# ArduinoProMini_NRF24_DHT.net
KiCad netlist of a schematic drawn in EAGLE
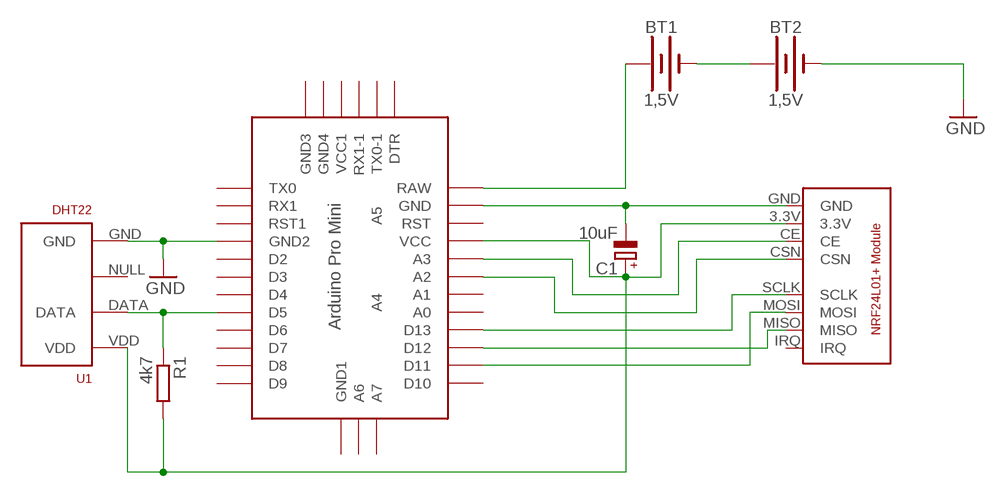
[diagram p0: schematic, sheet 1]

(export (version "E")
  (design (tool "Eeschema 10.0.6"))
  (components
    (comp (ref "BT1")
      (value "1,5V")
      (footprint "eagle-import:BATTERY-AA")
      (libsource (lib "eagle-import") (part "BATTERY-AA"))
    )
    (comp (ref "BT2")
      (value "1,5V")
      (footprint "eagle-import:BATTERY-AA")
      (libsource (lib "eagle-import") (part "BATTERY-AA"))
    )
    (comp (ref "C1")
      (value "10uF")
      (footprint "eagle-import:E2-5")
      (libsource (lib "eagle-import") (part "CPOL-EUE2-5"))
    )
    (comp (ref "R1")
      (value "4k7")
      (footprint "eagle-import:0204_7")
      (libsource (lib "eagle-import") (part "R-EU_0204/7"))
    )
    (comp (ref "U$1")
      (value "ABK-PRO-MINI")
      (footprint "eagle-import:ABK-PRO-MINI")
      (libsource (lib "eagle-import") (part "ABK-PRO-MINI"))
    )
    (comp (ref "U$2")
      (value "NRF24L01+MODULE")
      (footprint "eagle-import:NRF24L01+MODULE")
      (libsource (lib "eagle-import") (part "NRF24L01+MODULE"))
    )
    (comp (ref "U1")
      (value "DHT22")
      (footprint "eagle-import:RHT03_DHT-22_RA")
      (libsource (lib "eagle-import") (part "RHT03_DHT-22_AM2302RA"))
    )
  )
  (nets
    (net (code "1") (name "GND") (class "Default")
      (node (ref "BT2") (pin "GND@1") (pinfunction "-_GND@1") (pintype "power_in"))
      (node (ref "C1") (pin "-") (pinfunction "-_-") (pintype "passive"))
      (node (ref "U$1") (pin "GND") (pinfunction "GND_GND") (pintype "bidirectional"))
      (node (ref "U$1") (pin "GND1") (pinfunction "GND2_GND1") (pintype "bidirectional"))
      (node (ref "U$2") (pin "GND") (pinfunction "GND_GND") (pintype "power_in"))
      (node (ref "U1") (pin "GND") (pinfunction "GND_GND") (pintype "power_in"))
    )
    (net (code "2") (name "Net-(BT1-+)") (class "Default")
      (node (ref "BT1") (pin "PWR@1") (pinfunction "+_PWR@1") (pintype "power_in"))
      (node (ref "U$1") (pin "RAW") (pinfunction "RAW_RAW") (pintype "bidirectional"))
    )
    (net (code "3") (name "Net-(BT1--)") (class "Default")
      (node (ref "BT1") (pin "GND@1") (pinfunction "-_GND@1") (pintype "power_in"))
      (node (ref "BT2") (pin "PWR@1") (pinfunction "+_PWR@1") (pintype "power_in"))
    )
    (net (code "4") (name "Net-(C1-Pad+)") (class "Default")
      (node (ref "C1") (pin "+") (pinfunction "+_+") (pintype "passive"))
      (node (ref "R1") (pin "2") (pinfunction "2_2") (pintype "passive"))
      (node (ref "U$1") (pin "VCC") (pinfunction "VCC_VCC") (pintype "bidirectional"))
      (node (ref "U$2") (pin "3.3V") (pinfunction "3.3V_3.3V") (pintype "power_in"))
      (node (ref "U1") (pin "VDD") (pinfunction "VDD_VDD") (pintype "power_in"))
    )
    (net (code "5") (name "Net-(R1-Pad1)") (class "Default")
      (node (ref "R1") (pin "1") (pinfunction "1_1") (pintype "passive"))
      (node (ref "U$1") (pin "D5") (pinfunction "D5_D5") (pintype "bidirectional"))
      (node (ref "U1") (pin "DATA") (pinfunction "DATA_DATA") (pintype "bidirectional"))
    )
    (net (code "6") (name "Net-(U$1-PadA2)") (class "Default")
      (node (ref "U$1") (pin "A2") (pinfunction "A2_A2") (pintype "bidirectional"))
      (node (ref "U$2") (pin "CSN") (pinfunction "CSN_CSN") (pintype "bidirectional"))
    )
    (net (code "7") (name "Net-(U$1-PadA3)") (class "Default")
      (node (ref "U$1") (pin "A3") (pinfunction "A3_A3") (pintype "bidirectional"))
      (node (ref "U$2") (pin "CE") (pinfunction "CE_CE") (pintype "bidirectional"))
    )
    (net (code "8") (name "Net-(U$1-PadD11)") (class "Default")
      (node (ref "U$1") (pin "D11") (pinfunction "D11_D11") (pintype "bidirectional"))
      (node (ref "U$2") (pin "MOSI") (pinfunction "MOSI_MOSI") (pintype "bidirectional"))
    )
    (net (code "9") (name "Net-(U$1-PadD12)") (class "Default")
      (node (ref "U$1") (pin "D12") (pinfunction "D12_D12") (pintype "bidirectional"))
      (node (ref "U$2") (pin "MISO") (pinfunction "MISO_MISO") (pintype "bidirectional"))
    )
    (net (code "10") (name "Net-(U$1-PadD13)") (class "Default")
      (node (ref "U$1") (pin "D13") (pinfunction "D13_D13") (pintype "bidirectional"))
      (node (ref "U$2") (pin "SCLK") (pinfunction "SCLK_SCLK") (pintype "bidirectional"))
    )
    (net (code "11") (name "unconnected-(U$1-GND1-PadGND4)") (class "Default")
      (node (ref "U$1") (pin "GND4") (pinfunction "GND1_GND4") (pintype "bidirectional"))
    )
    (net (code "12") (name "unconnected-(U$1-GND3-PadGND2)") (class "Default")
      (node (ref "U$1") (pin "GND2") (pinfunction "GND3_GND2") (pintype "bidirectional"))
    )
    (net (code "13") (name "unconnected-(U$1-GND4-PadGND3)") (class "Default")
      (node (ref "U$1") (pin "GND3") (pinfunction "GND4_GND3") (pintype "bidirectional"))
    )
    (net (code "14") (name "unconnected-(U$1-PadA0)") (class "Default")
      (node (ref "U$1") (pin "A0") (pinfunction "A0_A0") (pintype "bidirectional"))
    )
    (net (code "15") (name "unconnected-(U$1-PadA1)") (class "Default")
      (node (ref "U$1") (pin "A1") (pinfunction "A1_A1") (pintype "bidirectional"))
    )
    (net (code "16") (name "unconnected-(U$1-PadA4)") (class "Default")
      (node (ref "U$1") (pin "A4") (pinfunction "A4_A4") (pintype "bidirectional"))
    )
    (net (code "17") (name "unconnected-(U$1-PadA5)") (class "Default")
      (node (ref "U$1") (pin "A5") (pinfunction "A5_A5") (pintype "bidirectional"))
    )
    (net (code "18") (name "unconnected-(U$1-PadA6)") (class "Default")
      (node (ref "U$1") (pin "A6") (pinfunction "A6_A6") (pintype "bidirectional"))
    )
    (net (code "19") (name "unconnected-(U$1-PadA7)") (class "Default")
      (node (ref "U$1") (pin "A7") (pinfunction "A7_A7") (pintype "bidirectional"))
    )
    (net (code "20") (name "unconnected-(U$1-PadD2)") (class "Default")
      (node (ref "U$1") (pin "D2") (pinfunction "D2_D2") (pintype "bidirectional"))
    )
    (net (code "21") (name "unconnected-(U$1-PadD3)") (class "Default")
      (node (ref "U$1") (pin "D3") (pinfunction "D3_D3") (pintype "bidirectional"))
    )
    (net (code "22") (name "unconnected-(U$1-PadD4)") (class "Default")
      (node (ref "U$1") (pin "D4") (pinfunction "D4_D4") (pintype "bidirectional"))
    )
    (net (code "23") (name "unconnected-(U$1-PadD6)") (class "Default")
      (node (ref "U$1") (pin "D6") (pinfunction "D6_D6") (pintype "bidirectional"))
    )
    (net (code "24") (name "unconnected-(U$1-PadD7)") (class "Default")
      (node (ref "U$1") (pin "D7") (pinfunction "D7_D7") (pintype "bidirectional"))
    )
    (net (code "25") (name "unconnected-(U$1-PadD8)") (class "Default")
      (node (ref "U$1") (pin "D8") (pinfunction "D8_D8") (pintype "bidirectional"))
    )
    (net (code "26") (name "unconnected-(U$1-PadD9)") (class "Default")
      (node (ref "U$1") (pin "D9") (pinfunction "D9_D9") (pintype "bidirectional"))
    )
    (net (code "27") (name "unconnected-(U$1-PadD10)") (class "Default")
      (node (ref "U$1") (pin "D10") (pinfunction "D10_D10") (pintype "bidirectional"))
    )
    (net (code "28") (name "unconnected-(U$1-PadDTR)") (class "Default")
      (node (ref "U$1") (pin "DTR") (pinfunction "DTR_DTR") (pintype "bidirectional"))
    )
    (net (code "29") (name "unconnected-(U$1-PadRST)") (class "Default")
      (node (ref "U$1") (pin "RST") (pinfunction "RST_RST") (pintype "bidirectional"))
    )
    (net (code "30") (name "unconnected-(U$1-PadRST1)") (class "Default")
      (node (ref "U$1") (pin "RST1") (pinfunction "RST1_RST1") (pintype "bidirectional"))
    )
    (net (code "31") (name "unconnected-(U$1-PadRX1)") (class "Default")
      (node (ref "U$1") (pin "RX1") (pinfunction "RX1_RX1") (pintype "bidirectional"))
    )
    (net (code "32") (name "unconnected-(U$1-PadRX1-1)") (class "Default")
      (node (ref "U$1") (pin "RX1-1") (pinfunction "RX1-1_RX1-1") (pintype "bidirectional"))
    )
    (net (code "33") (name "unconnected-(U$1-PadTX0)") (class "Default")
      (node (ref "U$1") (pin "TX0") (pinfunction "TX0_TX0") (pintype "bidirectional"))
    )
    (net (code "34") (name "unconnected-(U$1-PadTX0-1)") (class "Default")
      (node (ref "U$1") (pin "TX0-1") (pinfunction "TX0-1_TX0-1") (pintype "bidirectional"))
    )
    (net (code "35") (name "unconnected-(U$1-PadVCC1)") (class "Default")
      (node (ref "U$1") (pin "VCC1") (pinfunction "VCC1_VCC1") (pintype "bidirectional"))
    )
    (net (code "36") (name "unconnected-(U$2-PadIRQ)") (class "Default")
      (node (ref "U$2") (pin "IRQ") (pinfunction "IRQ_IRQ") (pintype "bidirectional"))
    )
    (net (code "37") (name "unconnected-(U1-PadNULL)") (class "Default")
      (node (ref "U1") (pin "NULL") (pinfunction "NULL_NULL") (pintype "no_connect"))
    )
  )
)
